# pmod-eight-led.net
KiCad netlist of a schematic drawn in EAGLE
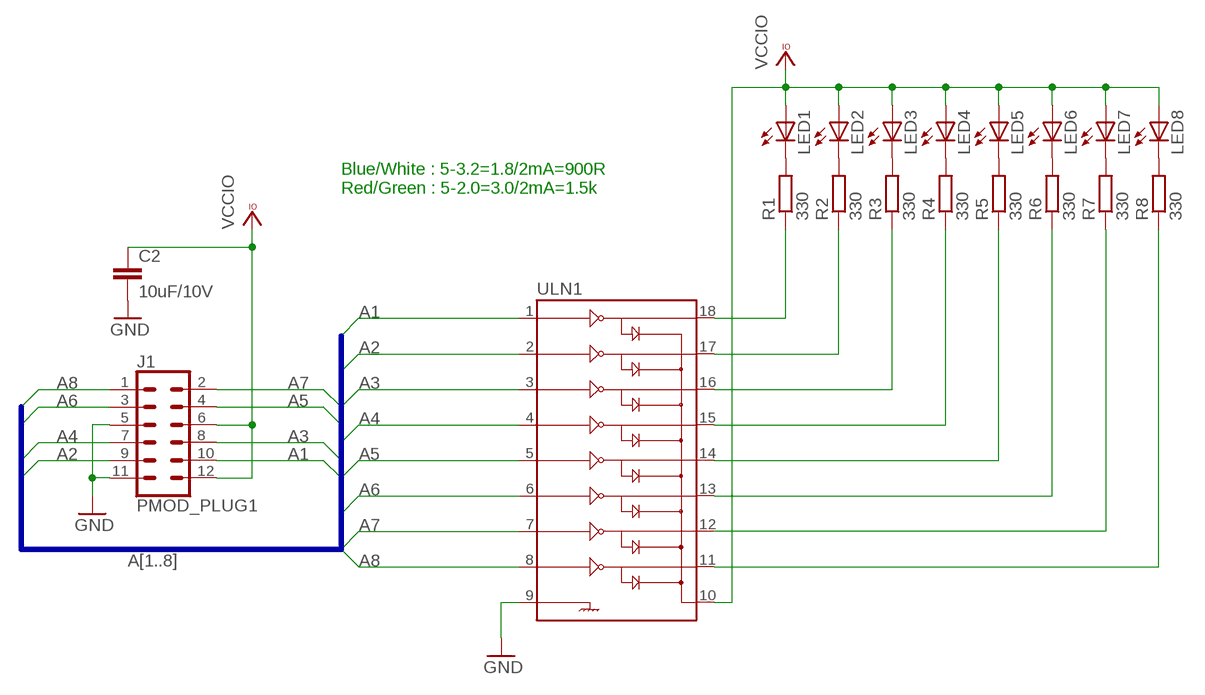
[diagram p0: schematic, sheet 1]

(export (version "E")
  (design (tool "Eeschema 10.0.6"))
  (components
    (comp (ref "C2")
      (value "10uF/10V")
      (footprint "eagle-import:C0805K")
      (libsource (lib "eagle-import") (part "C-EUC0805K"))
    )
    (comp (ref "J1")
      (value "PMOD_PLUG1")
      (footprint "eagle-import:2X6_SMD_RA_PLUG")
      (libsource (lib "eagle-import") (part "CONN_06X2SMD_RA_PLUG"))
    )
    (comp (ref "LED1")
      (value "LED0603")
      (footprint "eagle-import:LED-603")
      (libsource (lib "eagle-import") (part "LED0603"))
    )
    (comp (ref "LED2")
      (value "LED0603")
      (footprint "eagle-import:LED-603")
      (libsource (lib "eagle-import") (part "LED0603"))
    )
    (comp (ref "LED3")
      (value "LED0603")
      (footprint "eagle-import:LED-603")
      (libsource (lib "eagle-import") (part "LED0603"))
    )
    (comp (ref "LED4")
      (value "LED0603")
      (footprint "eagle-import:LED-603")
      (libsource (lib "eagle-import") (part "LED0603"))
    )
    (comp (ref "LED5")
      (value "LED0603")
      (footprint "eagle-import:LED-603")
      (libsource (lib "eagle-import") (part "LED0603"))
    )
    (comp (ref "LED6")
      (value "LED0603")
      (footprint "eagle-import:LED-603")
      (libsource (lib "eagle-import") (part "LED0603"))
    )
    (comp (ref "LED7")
      (value "LED0603")
      (footprint "eagle-import:LED-603")
      (libsource (lib "eagle-import") (part "LED0603"))
    )
    (comp (ref "LED8")
      (value "LED0603")
      (footprint "eagle-import:LED-603")
      (libsource (lib "eagle-import") (part "LED0603"))
    )
    (comp (ref "R1")
      (value "330")
      (footprint "eagle-import:R0805W")
      (libsource (lib "eagle-import") (part "R-EU_R0805W"))
    )
    (comp (ref "R2")
      (value "330")
      (footprint "eagle-import:R0805W")
      (libsource (lib "eagle-import") (part "R-EU_R0805W"))
    )
    (comp (ref "R3")
      (value "330")
      (footprint "eagle-import:R0805W")
      (libsource (lib "eagle-import") (part "R-EU_R0805W"))
    )
    (comp (ref "R4")
      (value "330")
      (footprint "eagle-import:R0805W")
      (libsource (lib "eagle-import") (part "R-EU_R0805W"))
    )
    (comp (ref "R5")
      (value "330")
      (footprint "eagle-import:R0805W")
      (libsource (lib "eagle-import") (part "R-EU_R0805W"))
    )
    (comp (ref "R6")
      (value "330")
      (footprint "eagle-import:R0805W")
      (libsource (lib "eagle-import") (part "R-EU_R0805W"))
    )
    (comp (ref "R7")
      (value "330")
      (footprint "eagle-import:R0805W")
      (libsource (lib "eagle-import") (part "R-EU_R0805W"))
    )
    (comp (ref "R8")
      (value "330")
      (footprint "eagle-import:R0805W")
      (libsource (lib "eagle-import") (part "R-EU_R0805W"))
    )
    (comp (ref "ULN1")
      (value "ULN2803SOICW")
      (footprint "eagle-import:SO18L")
      (libsource (lib "eagle-import") (part "ULN2803SOICW"))
    )
  )
  (nets
    (net (code "1") (name "/A1") (class "Default")
      (node (ref "J1") (pin "10") (pinfunction "10_10") (pintype "passive"))
      (node (ref "ULN1") (pin "1") (pinfunction "1_1") (pintype "bidirectional"))
    )
    (net (code "2") (name "/A2") (class "Default")
      (node (ref "J1") (pin "9") (pinfunction "9_9") (pintype "passive"))
      (node (ref "ULN1") (pin "2") (pinfunction "2_2") (pintype "bidirectional"))
    )
    (net (code "3") (name "/A3") (class "Default")
      (node (ref "J1") (pin "8") (pinfunction "8_8") (pintype "passive"))
      (node (ref "ULN1") (pin "3") (pinfunction "3_3") (pintype "bidirectional"))
    )
    (net (code "4") (name "/A4") (class "Default")
      (node (ref "J1") (pin "7") (pinfunction "7_7") (pintype "passive"))
      (node (ref "ULN1") (pin "4") (pinfunction "4_4") (pintype "bidirectional"))
    )
    (net (code "5") (name "/A5") (class "Default")
      (node (ref "J1") (pin "4") (pinfunction "4_4") (pintype "passive"))
      (node (ref "ULN1") (pin "5") (pinfunction "5_5") (pintype "bidirectional"))
    )
    (net (code "6") (name "/A6") (class "Default")
      (node (ref "J1") (pin "3") (pinfunction "3_3") (pintype "passive"))
      (node (ref "ULN1") (pin "6") (pinfunction "6_6") (pintype "bidirectional"))
    )
    (net (code "7") (name "/A7") (class "Default")
      (node (ref "J1") (pin "2") (pinfunction "2_2") (pintype "passive"))
      (node (ref "ULN1") (pin "7") (pinfunction "7_7") (pintype "bidirectional"))
    )
    (net (code "8") (name "/A8") (class "Default")
      (node (ref "J1") (pin "1") (pinfunction "1_1") (pintype "passive"))
      (node (ref "ULN1") (pin "8") (pinfunction "8_8") (pintype "bidirectional"))
    )
    (net (code "10") (name "GND") (class "Default")
      (node (ref "C2") (pin "2") (pinfunction "2_2") (pintype "passive"))
      (node (ref "J1") (pin "11") (pinfunction "11_11") (pintype "passive"))
      (node (ref "J1") (pin "5") (pinfunction "5_5") (pintype "passive"))
      (node (ref "ULN1") (pin "9") (pinfunction "9_9") (pintype "bidirectional"))
    )
    (net (code "11") (name "Net-(LED1-PadC)") (class "Default")
      (node (ref "LED1") (pin "C") (pinfunction "C_C") (pintype "passive"))
      (node (ref "R1") (pin "2") (pinfunction "2_2") (pintype "passive"))
    )
    (net (code "12") (name "Net-(LED2-PadC)") (class "Default")
      (node (ref "LED2") (pin "C") (pinfunction "C_C") (pintype "passive"))
      (node (ref "R2") (pin "2") (pinfunction "2_2") (pintype "passive"))
    )
    (net (code "13") (name "Net-(LED3-PadC)") (class "Default")
      (node (ref "LED3") (pin "C") (pinfunction "C_C") (pintype "passive"))
      (node (ref "R3") (pin "2") (pinfunction "2_2") (pintype "passive"))
    )
    (net (code "14") (name "Net-(LED4-PadC)") (class "Default")
      (node (ref "LED4") (pin "C") (pinfunction "C_C") (pintype "passive"))
      (node (ref "R4") (pin "2") (pinfunction "2_2") (pintype "passive"))
    )
    (net (code "15") (name "Net-(LED5-PadC)") (class "Default")
      (node (ref "LED5") (pin "C") (pinfunction "C_C") (pintype "passive"))
      (node (ref "R5") (pin "2") (pinfunction "2_2") (pintype "passive"))
    )
    (net (code "16") (name "Net-(LED6-PadC)") (class "Default")
      (node (ref "LED6") (pin "C") (pinfunction "C_C") (pintype "passive"))
      (node (ref "R6") (pin "2") (pinfunction "2_2") (pintype "passive"))
    )
    (net (code "17") (name "Net-(LED7-PadC)") (class "Default")
      (node (ref "LED7") (pin "C") (pinfunction "C_C") (pintype "passive"))
      (node (ref "R7") (pin "2") (pinfunction "2_2") (pintype "passive"))
    )
    (net (code "18") (name "Net-(LED8-PadC)") (class "Default")
      (node (ref "LED8") (pin "C") (pinfunction "C_C") (pintype "passive"))
      (node (ref "R8") (pin "2") (pinfunction "2_2") (pintype "passive"))
    )
    (net (code "19") (name "Net-(R1-Pad1)") (class "Default")
      (node (ref "R1") (pin "1") (pinfunction "1_1") (pintype "passive"))
      (node (ref "ULN1") (pin "18") (pinfunction "18_18") (pintype "bidirectional"))
    )
    (net (code "20") (name "Net-(R2-Pad1)") (class "Default")
      (node (ref "R2") (pin "1") (pinfunction "1_1") (pintype "passive"))
      (node (ref "ULN1") (pin "17") (pinfunction "17_17") (pintype "bidirectional"))
    )
    (net (code "21") (name "Net-(R3-Pad1)") (class "Default")
      (node (ref "R3") (pin "1") (pinfunction "1_1") (pintype "passive"))
      (node (ref "ULN1") (pin "16") (pinfunction "16_16") (pintype "bidirectional"))
    )
    (net (code "22") (name "Net-(R4-Pad1)") (class "Default")
      (node (ref "R4") (pin "1") (pinfunction "1_1") (pintype "passive"))
      (node (ref "ULN1") (pin "15") (pinfunction "15_15") (pintype "bidirectional"))
    )
    (net (code "23") (name "Net-(R5-Pad1)") (class "Default")
      (node (ref "R5") (pin "1") (pinfunction "1_1") (pintype "passive"))
      (node (ref "ULN1") (pin "14") (pinfunction "14_14") (pintype "bidirectional"))
    )
    (net (code "24") (name "Net-(R6-Pad1)") (class "Default")
      (node (ref "R6") (pin "1") (pinfunction "1_1") (pintype "passive"))
      (node (ref "ULN1") (pin "13") (pinfunction "13_13") (pintype "bidirectional"))
    )
    (net (code "25") (name "Net-(R7-Pad1)") (class "Default")
      (node (ref "R7") (pin "1") (pinfunction "1_1") (pintype "passive"))
      (node (ref "ULN1") (pin "12") (pinfunction "12_12") (pintype "bidirectional"))
    )
    (net (code "26") (name "Net-(R8-Pad1)") (class "Default")
      (node (ref "R8") (pin "1") (pinfunction "1_1") (pintype "passive"))
      (node (ref "ULN1") (pin "11") (pinfunction "11_11") (pintype "bidirectional"))
    )
    (net (code "27") (name "VCCIO") (class "Default")
      (node (ref "C2") (pin "1") (pinfunction "1_1") (pintype "passive"))
      (node (ref "J1") (pin "12") (pinfunction "12_12") (pintype "passive"))
      (node (ref "J1") (pin "6") (pinfunction "6_6") (pintype "passive"))
      (node (ref "LED1") (pin "A") (pinfunction "A_A") (pintype "passive"))
      (node (ref "LED2") (pin "A") (pinfunction "A_A") (pintype "passive"))
      (node (ref "LED3") (pin "A") (pinfunction "A_A") (pintype "passive"))
      (node (ref "LED4") (pin "A") (pinfunction "A_A") (pintype "passive"))
      (node (ref "LED5") (pin "A") (pinfunction "A_A") (pintype "passive"))
      (node (ref "LED6") (pin "A") (pinfunction "A_A") (pintype "passive"))
      (node (ref "LED7") (pin "A") (pinfunction "A_A") (pintype "passive"))
      (node (ref "LED8") (pin "A") (pinfunction "A_A") (pintype "passive"))
      (node (ref "ULN1") (pin "10") (pinfunction "10_10") (pintype "bidirectional"))
    )
  )
)
